# led_matrix_board.net
KiCad netlist of a schematic drawn in Altium Designer
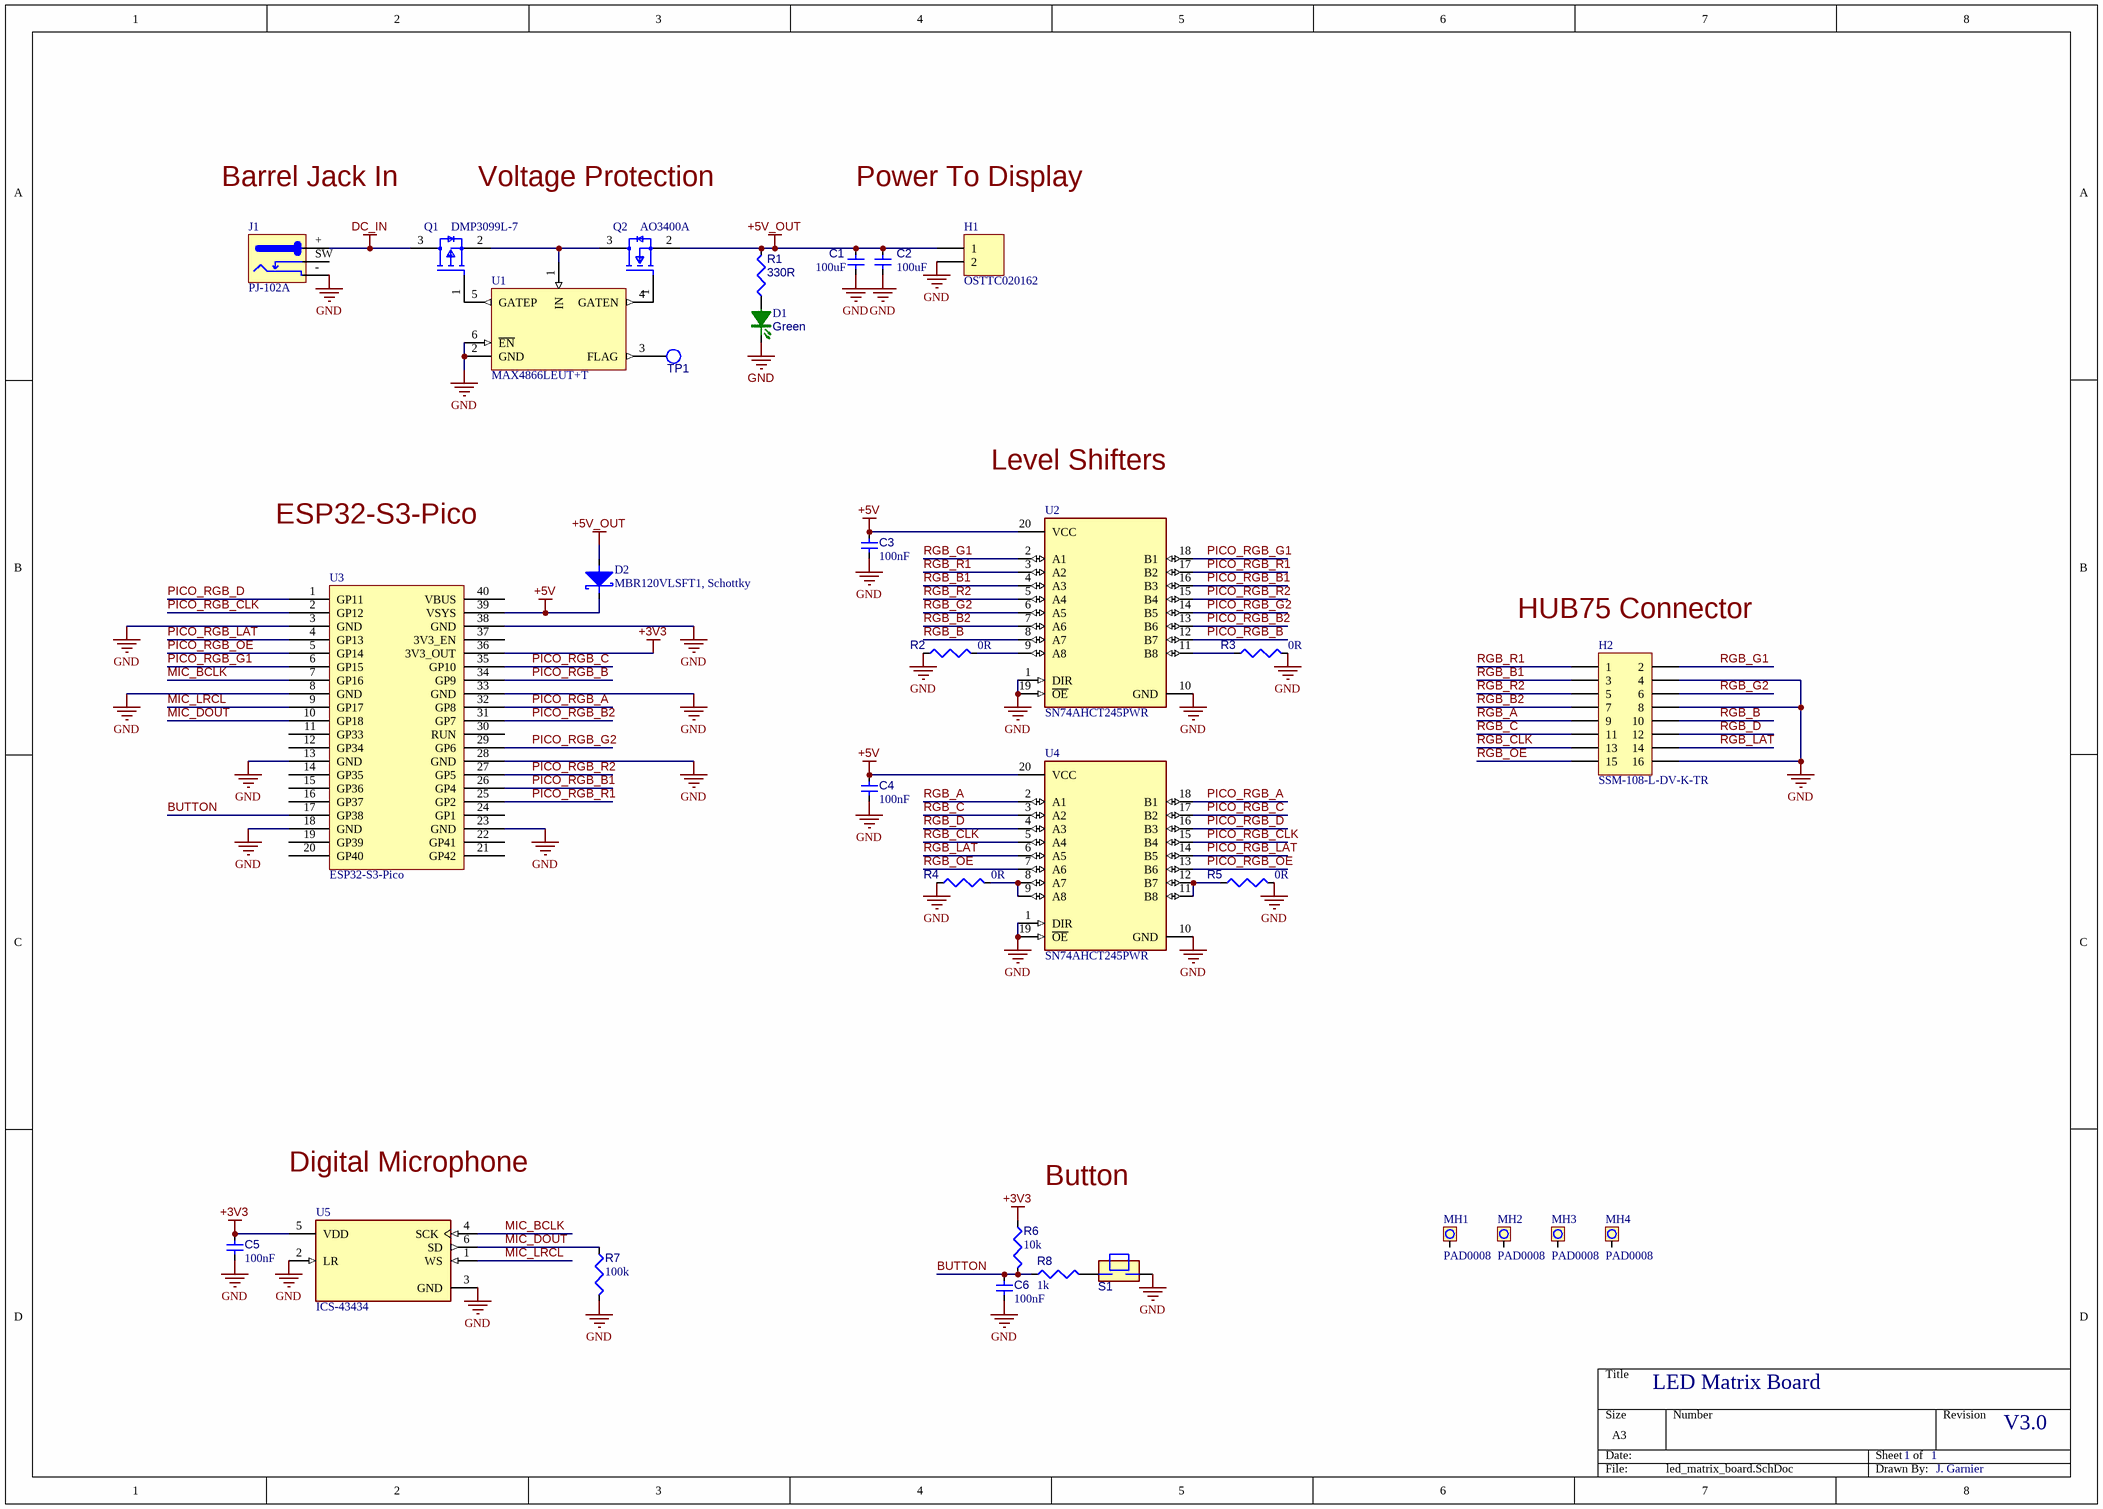
[diagram p0: led_matrix_board.SchDoc]

(export (version "E")
  (design (tool "Eeschema 10.0.6"))
  (components
    (comp (ref "C1")
      (value "100uF")
      (footprint "CAPC3225X20N")
      (description "CAP CER 100UF 10V ±20% X5R 1210")
      (fields (field (name "TOLERANCE") "20%") (field (name "VOLTAGE") "10V"))
      (libsource (lib "Morse Micro Pty Limited") (part "CAP"))
    )
    (comp (ref "C2")
      (value "100uF")
      (footprint "CAPC3225X20N")
      (description "CAP CER 100UF 10V ±20% X5R 1210")
      (fields (field (name "TOLERANCE") "20%") (field (name "VOLTAGE") "10V"))
      (libsource (lib "Morse Micro Pty Limited") (part "CAP"))
    )
    (comp (ref "C3")
      (value "100nF")
      (footprint "0603_cap")
      (description "CAP CER 100NF 10V ±10% X7R 0603")
      (fields (field (name "TOLERANCE") "10%") (field (name "VOLTAGE") "10V"))
      (libsource (lib "Morse Micro Pty Limited") (part "CAP"))
    )
    (comp (ref "C4")
      (value "100nF")
      (footprint "0603_cap")
      (description "CAP CER 100NF 10V ±10% X7R 0603")
      (fields (field (name "TOLERANCE") "10%") (field (name "VOLTAGE") "10V"))
      (libsource (lib "Morse Micro Pty Limited") (part "CAP"))
    )
    (comp (ref "C5")
      (value "100nF")
      (footprint "0603_cap")
      (description "CAP CER 100NF 10V ±10% X7R 0603")
      (fields (field (name "TOLERANCE") "10%") (field (name "VOLTAGE") "10V"))
      (libsource (lib "Morse Micro Pty Limited") (part "CAP"))
    )
    (comp (ref "C6")
      (value "100nF")
      (footprint "0603_cap")
      (description "CAP CER 100NF 10V ±10% X7R 0603")
      (fields (field (name "TOLERANCE") "10%") (field (name "VOLTAGE") "10V"))
      (libsource (lib "Morse Micro Pty Limited") (part "CAP"))
    )
    (comp (ref "D1")
      (value "Green")
      (footprint "LED_0402_GREEN")
      (description "LED GREEN 0402 SMD")
      (fields (field (name "VOLTAGE") "2.0V") (field (name "Comment") "XZVGR68W-3"))
      (libsource (lib "Morse Micro Pty Limited") (part "LED_G"))
    )
    (comp (ref "D2")
      (value "MBR120VLSFT1, Schottky")
      (footprint "SOD-123FL")
      (description "Diodes, MBR120VLSFT1 Schottky 1A 20V, Vf=0.34V")
      (fields (field (name "VOLTAGE") "20V") (field (name "Comment") "MBR120VLSFT1"))
      (libsource (lib "Morse Micro Pty Limited") (part "SCHOTTKY_DIODE"))
    )
    (comp (ref "H1")
      (value "OSTTC020162")
      (footprint "SCREW_TERM_2WAY_5MM")
      (description "CONN TERM BLOCK 5MM 2POS")
      (libsource (lib "Morse Micro Pty Limited") (part "HDR_1X2"))
    )
    (comp (ref "H2")
      (value "SSM-108-L-DV-K-TR")
      (footprint "FP-SSM-108-L-DV-K-TR-MFG")
      (description "PCB Receptacle, Board-to-Board, 2.54 mm, 2 Rows, 16 Contacts, Surface Mount")
      (libsource (lib "Morse Micro Pty Limited") (part "HDR_2X8"))
    )
    (comp (ref "J1")
      (value "PJ-102A")
      (footprint "PJ-102A")
      (description "Conn Power Jack 2.1mm PCB Mount Thru-Hole")
      (libsource (lib "Morse Micro Pty Limited") (part "2_1MM POWER"))
    )
    (comp (ref "MH1")
      (value "PAD0008")
      (footprint "MH_600_320_NPTH")
      (description "MH 6.00MM DIA 3.2MM HOLE NPTH")
      (libsource (lib "Morse Micro Pty Limited") (part "MH_600_320_NPTH"))
    )
    (comp (ref "MH2")
      (value "PAD0008")
      (footprint "MH_600_320_NPTH")
      (description "MH 6.00MM DIA 3.2MM HOLE NPTH")
      (libsource (lib "Morse Micro Pty Limited") (part "MH_600_320_NPTH"))
    )
    (comp (ref "MH3")
      (value "PAD0008")
      (footprint "MH_600_320_NPTH")
      (description "MH 6.00MM DIA 3.2MM HOLE NPTH")
      (libsource (lib "Morse Micro Pty Limited") (part "MH_600_320_NPTH"))
    )
    (comp (ref "MH4")
      (value "PAD0008")
      (footprint "MH_600_320_NPTH")
      (description "MH 6.00MM DIA 3.2MM HOLE NPTH")
      (libsource (lib "Morse Micro Pty Limited") (part "MH_600_320_NPTH"))
    )
    (comp (ref "Q1")
      (value "DMP3099L-7")
      (footprint "FP-SOT23-IPC_C")
      (description "DMP3099L Series 30 V 65 mOhm P-Channel Enhancement Mode Mosfet - SOT-23-3")
      (libsource (lib "Morse Micro Pty Limited") (part "d876440acba04c58a9f817a20952145"))
    )
    (comp (ref "Q2")
      (value "AO3400A")
      (footprint "FP-SOT23-IPC_C")
      (description "Trans MOSFET N-CH 30V 5.7A 3-Pin SOT-23")
      (libsource (lib "Morse Micro Pty Limited") (part "0a9ea7c96deaaede766a5b531c28de0"))
    )
    (comp (ref "R1")
      (value "330R")
      (footprint "0402_res")
      (description "RES SMD 330R OHM ±1% 1/16W 0402")
      (fields (field (name "POWER") "1/16W") (field (name "TOLERANCE") "1%"))
      (libsource (lib "Morse Micro Pty Limited") (part "RES"))
    )
    (comp (ref "R2")
      (value "0R")
      (footprint "0603_res")
      (description "RES SMD 0R OHM ±1% 1/10W 0603")
      (fields (field (name "TOLERANCE") "1%") (field (name "POWER") "1/10W"))
      (libsource (lib "Morse Micro Pty Limited") (part "RES"))
    )
    (comp (ref "R3")
      (value "0R")
      (footprint "0603_res")
      (description "RES SMD 0R OHM ±1% 1/10W 0603")
      (fields (field (name "TOLERANCE") "1%") (field (name "POWER") "1/10W"))
      (libsource (lib "Morse Micro Pty Limited") (part "RES"))
    )
    (comp (ref "R4")
      (value "0R")
      (footprint "0603_res")
      (description "RES SMD 0R OHM ±1% 1/10W 0603")
      (fields (field (name "TOLERANCE") "1%") (field (name "POWER") "1/10W"))
      (libsource (lib "Morse Micro Pty Limited") (part "RES"))
    )
    (comp (ref "R5")
      (value "0R")
      (footprint "0603_res")
      (description "RES SMD 0R OHM ±1% 1/10W 0603")
      (fields (field (name "TOLERANCE") "1%") (field (name "POWER") "1/10W"))
      (libsource (lib "Morse Micro Pty Limited") (part "RES"))
    )
    (comp (ref "R6")
      (value "10k")
      (footprint "0603_res")
      (description "RES SMD 10K OHM ±1% 1/10W 0603")
      (fields (field (name "POWER") "1/10W") (field (name "TOLERANCE") "1%"))
      (libsource (lib "Morse Micro Pty Limited") (part "RES"))
    )
    (comp (ref "R7")
      (value "100k")
      (footprint "0603_res")
      (description "RES SMD 100K OHM ±1% 1/10W 0603")
      (fields (field (name "POWER") "1/10W") (field (name "TOLERANCE") "1%"))
      (libsource (lib "Morse Micro Pty Limited") (part "RES"))
    )
    (comp (ref "R8")
      (value "1k")
      (footprint "0603_res")
      (description "RES SMD 1K OHM ±0 .1% 1/10W 0603")
      (fields (field (name "TOLERANCE") "0 .1%") (field (name "POWER") "1/10W"))
      (libsource (lib "Morse Micro Pty Limited") (part "RES"))
    )
    (comp (ref "S1")
      (value "EVQ-PF206K")
      (footprint "EVQ-PF206K")
      (description "SW, Tactile 15V@20mA, EVQ-PF, Through Hole, R/A, 7.5x7.1x5.85mm")
      (libsource (lib "Morse Micro Pty Limited") (part "SW_PB"))
    )
    (comp (ref "TP1")
      (value "PAD0035")
      (footprint "TP_40_SMT")
      (description "40mil 1mm SMD Test Point")
      (libsource (lib "Morse Micro Pty Limited") (part "TP_20_SMT"))
    )
    (comp (ref "U1")
      (value "MAX4866LEUT+T")
      (footprint "MAX4866LEUT+T-Footprint-1")
      (description "Overvoltage Protection Controllers with Reverse Polarity Protection")
      (libsource (lib "Morse Micro Pty Limited") (part "MAX4866LEUT+T-Symbol-1"))
    )
    (comp (ref "U2")
      (value "SN74AHCT245PWR")
      (footprint "FP-PW0020A-IPC_A")
      (description "8mA 8 4.5V~5.5V 8mA 1 TSSOP-20 Buffer/Driver/Transceiver ROHS")
      (libsource (lib "Morse Micro Pty Limited") (part "f8b0c07ade4f6b8d62f3b9458d8db27"))
    )
    (comp (ref "U3")
      (value "ESP32-S3-Pico")
      (footprint "ESP32-S3-Pico")
      (description "ESP32-S3-Pico Module.")
      (libsource (lib "Morse Micro Pty Limited") (part "ESP32-S3-Pico"))
    )
    (comp (ref "U4")
      (value "SN74AHCT245PWR")
      (footprint "FP-PW0020A-IPC_A")
      (description "8mA 8 4.5V~5.5V 8mA 1 TSSOP-20 Buffer/Driver/Transceiver ROHS")
      (libsource (lib "Morse Micro Pty Limited") (part "f8b0c07ade4f6b8d62f3b9458d8db27"))
    )
    (comp (ref "U5")
      (value "ICS-43434")
      (footprint "FP-ICS-43434-MFG")
      (description "Mic Omni-Directional -26dB 3.63V Rectangular Solder Pad T/R")
      (libsource (lib "Morse Micro Pty Limited") (part "ae05e933d23a1a1b08b70095a55dc98"))
    )
  )
  (nets
    (net (code "1") (name "+3V3") (class "Default")
      (node (ref "C5") (pin "1") (pinfunction "1_1") (pintype "passive"))
      (node (ref "R6") (pin "1") (pinfunction "1_1") (pintype "passive"))
      (node (ref "U3") (pin "36") (pinfunction "3V3_OUT_36") (pintype "passive"))
      (node (ref "U5") (pin "5") (pinfunction "VDD_5") (pintype "power_in"))
    )
    (net (code "2") (name "+5V") (class "Default")
      (node (ref "C3") (pin "1") (pinfunction "1_1") (pintype "passive"))
      (node (ref "C4") (pin "1") (pinfunction "1_1") (pintype "passive"))
      (node (ref "D2") (pin "K") (pinfunction "K_K") (pintype "passive"))
      (node (ref "U2") (pin "20") (pinfunction "VCC_20") (pintype "power_in"))
      (node (ref "U3") (pin "39") (pinfunction "VSYS_39") (pintype "passive"))
      (node (ref "U4") (pin "20") (pinfunction "VCC_20") (pintype "power_in"))
    )
    (net (code "3") (name "+5V_OUT") (class "Default")
      (node (ref "C1") (pin "1") (pinfunction "1_1") (pintype "passive"))
      (node (ref "C2") (pin "1") (pinfunction "1_1") (pintype "passive"))
      (node (ref "D2") (pin "A") (pinfunction "A_A") (pintype "passive"))
      (node (ref "H1") (pin "1") (pinfunction "1_1") (pintype "passive"))
      (node (ref "Q2") (pin "2") (pinfunction "S_2") (pintype "passive"))
      (node (ref "R1") (pin "2") (pinfunction "2_2") (pintype "passive"))
    )
    (net (code "4") (name "/BUTTON") (class "Default")
      (node (ref "C6") (pin "1") (pinfunction "1_1") (pintype "passive"))
      (node (ref "R6") (pin "2") (pinfunction "2_2") (pintype "passive"))
      (node (ref "R8") (pin "1") (pinfunction "1_1") (pintype "passive"))
      (node (ref "U3") (pin "17") (pinfunction "GP38_17") (pintype "passive"))
    )
    (net (code "5") (name "/MIC_BCLK") (class "Default")
      (node (ref "U3") (pin "7") (pinfunction "GP16_7") (pintype "passive"))
      (node (ref "U5") (pin "4") (pinfunction "SCK_4") (pintype "input"))
    )
    (net (code "6") (name "/MIC_DOUT") (class "Default")
      (node (ref "R7") (pin "1") (pinfunction "1_1") (pintype "passive"))
      (node (ref "U3") (pin "10") (pinfunction "GP18_10") (pintype "passive"))
      (node (ref "U5") (pin "6") (pinfunction "SD_6") (pintype "output"))
    )
    (net (code "7") (name "/MIC_LRCL") (class "Default")
      (node (ref "U3") (pin "9") (pinfunction "GP17_9") (pintype "passive"))
      (node (ref "U5") (pin "1") (pinfunction "WS_1") (pintype "input"))
    )
    (net (code "8") (name "/PICO_RGB_A") (class "Default")
      (node (ref "U3") (pin "32") (pinfunction "GP8_32") (pintype "passive"))
      (node (ref "U4") (pin "18") (pinfunction "B1_18") (pintype "bidirectional"))
    )
    (net (code "9") (name "/PICO_RGB_B") (class "Default")
      (node (ref "U2") (pin "12") (pinfunction "B7_12") (pintype "bidirectional"))
      (node (ref "U3") (pin "34") (pinfunction "GP9_34") (pintype "passive"))
    )
    (net (code "10") (name "/PICO_RGB_B1") (class "Default")
      (node (ref "U2") (pin "16") (pinfunction "B3_16") (pintype "bidirectional"))
      (node (ref "U3") (pin "26") (pinfunction "GP4_26") (pintype "passive"))
    )
    (net (code "11") (name "/PICO_RGB_B2") (class "Default")
      (node (ref "U2") (pin "13") (pinfunction "B6_13") (pintype "bidirectional"))
      (node (ref "U3") (pin "31") (pinfunction "GP7_31") (pintype "passive"))
    )
    (net (code "12") (name "/PICO_RGB_C") (class "Default")
      (node (ref "U3") (pin "35") (pinfunction "GP10_35") (pintype "passive"))
      (node (ref "U4") (pin "17") (pinfunction "B2_17") (pintype "bidirectional"))
    )
    (net (code "13") (name "/PICO_RGB_CLK") (class "Default")
      (node (ref "U3") (pin "2") (pinfunction "GP12_2") (pintype "passive"))
      (node (ref "U4") (pin "15") (pinfunction "B4_15") (pintype "bidirectional"))
    )
    (net (code "14") (name "/PICO_RGB_D") (class "Default")
      (node (ref "U3") (pin "1") (pinfunction "GP11_1") (pintype "passive"))
      (node (ref "U4") (pin "16") (pinfunction "B3_16") (pintype "bidirectional"))
    )
    (net (code "15") (name "/PICO_RGB_G1") (class "Default")
      (node (ref "U2") (pin "18") (pinfunction "B1_18") (pintype "bidirectional"))
      (node (ref "U3") (pin "6") (pinfunction "GP15_6") (pintype "passive"))
    )
    (net (code "16") (name "/PICO_RGB_G2") (class "Default")
      (node (ref "U2") (pin "14") (pinfunction "B5_14") (pintype "bidirectional"))
      (node (ref "U3") (pin "29") (pinfunction "GP6_29") (pintype "passive"))
    )
    (net (code "17") (name "/PICO_RGB_LAT") (class "Default")
      (node (ref "U3") (pin "4") (pinfunction "GP13_4") (pintype "passive"))
      (node (ref "U4") (pin "14") (pinfunction "B5_14") (pintype "bidirectional"))
    )
    (net (code "18") (name "/PICO_RGB_OE") (class "Default")
      (node (ref "U3") (pin "5") (pinfunction "GP14_5") (pintype "passive"))
      (node (ref "U4") (pin "13") (pinfunction "B6_13") (pintype "bidirectional"))
    )
    (net (code "19") (name "/PICO_RGB_R1") (class "Default")
      (node (ref "U2") (pin "17") (pinfunction "B2_17") (pintype "bidirectional"))
      (node (ref "U3") (pin "25") (pinfunction "GP2_25") (pintype "passive"))
    )
    (net (code "20") (name "/PICO_RGB_R2") (class "Default")
      (node (ref "U2") (pin "15") (pinfunction "B4_15") (pintype "bidirectional"))
      (node (ref "U3") (pin "27") (pinfunction "GP5_27") (pintype "passive"))
    )
    (net (code "21") (name "/RGB_A") (class "Default")
      (node (ref "H2") (pin "9") (pinfunction "9_9") (pintype "passive"))
      (node (ref "U4") (pin "2") (pinfunction "A1_2") (pintype "bidirectional"))
    )
    (net (code "22") (name "/RGB_B") (class "Default")
      (node (ref "H2") (pin "10") (pinfunction "10_10") (pintype "passive"))
      (node (ref "U2") (pin "8") (pinfunction "A7_8") (pintype "bidirectional"))
    )
    (net (code "23") (name "/RGB_B1") (class "Default")
      (node (ref "H2") (pin "3") (pinfunction "3_3") (pintype "passive"))
      (node (ref "U2") (pin "4") (pinfunction "A3_4") (pintype "bidirectional"))
    )
    (net (code "24") (name "/RGB_B2") (class "Default")
      (node (ref "H2") (pin "7") (pinfunction "7_7") (pintype "passive"))
      (node (ref "U2") (pin "7") (pinfunction "A6_7") (pintype "bidirectional"))
    )
    (net (code "25") (name "/RGB_C") (class "Default")
      (node (ref "H2") (pin "11") (pinfunction "11_11") (pintype "passive"))
      (node (ref "U4") (pin "3") (pinfunction "A2_3") (pintype "bidirectional"))
    )
    (net (code "26") (name "/RGB_CLK") (class "Default")
      (node (ref "H2") (pin "13") (pinfunction "13_13") (pintype "passive"))
      (node (ref "U4") (pin "5") (pinfunction "A4_5") (pintype "bidirectional"))
    )
    (net (code "27") (name "/RGB_D") (class "Default")
      (node (ref "H2") (pin "12") (pinfunction "12_12") (pintype "passive"))
      (node (ref "U4") (pin "4") (pinfunction "A3_4") (pintype "bidirectional"))
    )
    (net (code "28") (name "/RGB_G1") (class "Default")
      (node (ref "H2") (pin "2") (pinfunction "2_2") (pintype "passive"))
      (node (ref "U2") (pin "2") (pinfunction "A1_2") (pintype "bidirectional"))
    )
    (net (code "29") (name "/RGB_G2") (class "Default")
      (node (ref "H2") (pin "6") (pinfunction "6_6") (pintype "passive"))
      (node (ref "U2") (pin "6") (pinfunction "A5_6") (pintype "bidirectional"))
    )
    (net (code "30") (name "/RGB_LAT") (class "Default")
      (node (ref "H2") (pin "14") (pinfunction "14_14") (pintype "passive"))
      (node (ref "U4") (pin "6") (pinfunction "A5_6") (pintype "bidirectional"))
    )
    (net (code "31") (name "/RGB_OE") (class "Default")
      (node (ref "H2") (pin "15") (pinfunction "15_15") (pintype "passive"))
      (node (ref "U4") (pin "7") (pinfunction "A6_7") (pintype "bidirectional"))
    )
    (net (code "32") (name "/RGB_R1") (class "Default")
      (node (ref "H2") (pin "1") (pinfunction "1_1") (pintype "passive"))
      (node (ref "U2") (pin "3") (pinfunction "A2_3") (pintype "bidirectional"))
    )
    (net (code "33") (name "/RGB_R2") (class "Default")
      (node (ref "H2") (pin "5") (pinfunction "5_5") (pintype "passive"))
      (node (ref "U2") (pin "5") (pinfunction "A4_5") (pintype "bidirectional"))
    )
    (net (code "34") (name "DC_IN") (class "Default")
      (node (ref "J1") (pin "+") (pinfunction "+_+") (pintype "passive"))
      (node (ref "Q1") (pin "3") (pinfunction "D_3") (pintype "passive"))
    )
    (net (code "35") (name "GND") (class "Default")
      (node (ref "C1") (pin "2") (pinfunction "2_2") (pintype "passive"))
      (node (ref "C2") (pin "2") (pinfunction "2_2") (pintype "passive"))
      (node (ref "C3") (pin "2") (pinfunction "2_2") (pintype "passive"))
      (node (ref "C4") (pin "2") (pinfunction "2_2") (pintype "passive"))
      (node (ref "C5") (pin "2") (pinfunction "2_2") (pintype "passive"))
      (node (ref "C6") (pin "2") (pinfunction "2_2") (pintype "passive"))
      (node (ref "D1") (pin "K") (pinfunction "2_K") (pintype "passive"))
      (node (ref "H1") (pin "2") (pinfunction "2_2") (pintype "passive"))
      (node (ref "H2") (pin "16") (pinfunction "16_16") (pintype "passive"))
      (node (ref "H2") (pin "4") (pinfunction "4_4") (pintype "passive"))
      (node (ref "H2") (pin "8") (pinfunction "8_8") (pintype "passive"))
      (node (ref "J1") (pin "-") (pinfunction "-_-") (pintype "passive"))
      (node (ref "R2") (pin "1") (pinfunction "1_1") (pintype "passive"))
      (node (ref "R3") (pin "1") (pinfunction "1_1") (pintype "passive"))
      (node (ref "R4") (pin "1") (pinfunction "1_1") (pintype "passive"))
      (node (ref "R5") (pin "2") (pinfunction "2_2") (pintype "passive"))
      (node (ref "R7") (pin "2") (pinfunction "2_2") (pintype "passive"))
      (node (ref "S1") (pin "2") (pinfunction "2_2") (pintype "passive"))
      (node (ref "U1") (pin "2") (pinfunction "GND_2") (pintype "power_in"))
      (node (ref "U1") (pin "6") (pinfunction "~{EN}_6") (pintype "input"))
      (node (ref "U2") (pin "1") (pinfunction "DIR_1") (pintype "input"))
      (node (ref "U2") (pin "10") (pinfunction "GND_10") (pintype "power_in"))
      (node (ref "U2") (pin "19") (pinfunction "~{OE}_19") (pintype "input"))
      (node (ref "U3") (pin "13") (pinfunction "GND_13") (pintype "passive"))
      (node (ref "U3") (pin "18") (pinfunction "GND_18") (pintype "passive"))
      (node (ref "U3") (pin "23") (pinfunction "GND_23") (pintype "passive"))
      (node (ref "U3") (pin "28") (pinfunction "GND_28") (pintype "passive"))
      (node (ref "U3") (pin "3") (pinfunction "GND_3") (pintype "passive"))
      (node (ref "U3") (pin "33") (pinfunction "GND_33") (pintype "passive"))
      (node (ref "U3") (pin "38") (pinfunction "GND_38") (pintype "passive"))
      (node (ref "U3") (pin "8") (pinfunction "GND_8") (pintype "passive"))
      (node (ref "U4") (pin "1") (pinfunction "DIR_1") (pintype "input"))
      (node (ref "U4") (pin "10") (pinfunction "GND_10") (pintype "power_in"))
      (node (ref "U4") (pin "19") (pinfunction "~{OE}_19") (pintype "input"))
      (node (ref "U5") (pin "2") (pinfunction "LR_2") (pintype "input"))
      (node (ref "U5") (pin "3") (pinfunction "GND_3") (pintype "power_in"))
    )
    (net (code "36") (name "Net-(D1-1)") (class "Default")
      (node (ref "D1") (pin "A") (pinfunction "1_A") (pintype "passive"))
      (node (ref "R1") (pin "1") (pinfunction "1_1") (pintype "passive"))
    )
    (net (code "37") (name "Net-(Q1-G)") (class "Default")
      (node (ref "Q1") (pin "1") (pinfunction "G_1") (pintype "passive"))
      (node (ref "U1") (pin "5") (pinfunction "GATEP_5") (pintype "output"))
    )
    (net (code "38") (name "Net-(Q1-S)") (class "Default")
      (node (ref "Q1") (pin "2") (pinfunction "S_2") (pintype "passive"))
      (node (ref "Q2") (pin "3") (pinfunction "D_3") (pintype "passive"))
      (node (ref "U1") (pin "1") (pinfunction "IN_1") (pintype "input"))
    )
    (net (code "39") (name "Net-(Q2-G)") (class "Default")
      (node (ref "Q2") (pin "1") (pinfunction "G_1") (pintype "passive"))
      (node (ref "U1") (pin "4") (pinfunction "GATEN_4") (pintype "output"))
    )
    (net (code "40") (name "Net-(R8-Pad2)") (class "Default")
      (node (ref "R8") (pin "2") (pinfunction "2_2") (pintype "passive"))
      (node (ref "S1") (pin "1") (pinfunction "1_1") (pintype "passive"))
    )
    (net (code "41") (name "Net-(U1-FLAG)") (class "Default")
      (node (ref "TP1") (pin "1") (pinfunction "1_1") (pintype "passive"))
      (node (ref "U1") (pin "3") (pinfunction "FLAG_3") (pintype "output"))
    )
    (net (code "42") (name "Net-(U2-A8)") (class "Default")
      (node (ref "R2") (pin "2") (pinfunction "2_2") (pintype "passive"))
      (node (ref "U2") (pin "9") (pinfunction "A8_9") (pintype "bidirectional"))
    )
    (net (code "43") (name "Net-(U2-B8)") (class "Default")
      (node (ref "R3") (pin "2") (pinfunction "2_2") (pintype "passive"))
      (node (ref "U2") (pin "11") (pinfunction "B8_11") (pintype "bidirectional"))
    )
    (net (code "44") (name "Net-(U4-A7)") (class "Default")
      (node (ref "R4") (pin "2") (pinfunction "2_2") (pintype "passive"))
      (node (ref "U4") (pin "8") (pinfunction "A7_8") (pintype "bidirectional"))
      (node (ref "U4") (pin "9") (pinfunction "A8_9") (pintype "bidirectional"))
    )
    (net (code "45") (name "Net-(U4-B7)") (class "Default")
      (node (ref "R5") (pin "1") (pinfunction "1_1") (pintype "passive"))
      (node (ref "U4") (pin "11") (pinfunction "B8_11") (pintype "bidirectional"))
      (node (ref "U4") (pin "12") (pinfunction "B7_12") (pintype "bidirectional"))
    )
    (net (code "46") (name "unconnected-(J1-PadSW)") (class "Default")
      (node (ref "J1") (pin "SW") (pinfunction "SW_SW") (pintype "passive"))
    )
    (net (code "47") (name "unconnected-(MH1-Pad1)") (class "Default")
      (node (ref "MH1") (pin "1") (pinfunction "1_1") (pintype "passive"))
    )
    (net (code "48") (name "unconnected-(MH2-Pad1)") (class "Default")
      (node (ref "MH2") (pin "1") (pinfunction "1_1") (pintype "passive"))
    )
    (net (code "49") (name "unconnected-(MH3-Pad1)") (class "Default")
      (node (ref "MH3") (pin "1") (pinfunction "1_1") (pintype "passive"))
    )
    (net (code "50") (name "unconnected-(MH4-Pad1)") (class "Default")
      (node (ref "MH4") (pin "1") (pinfunction "1_1") (pintype "passive"))
    )
    (net (code "51") (name "unconnected-(U3-3V3_EN-Pad37)") (class "Default")
      (node (ref "U3") (pin "37") (pinfunction "3V3_EN_37") (pintype "passive"))
    )
    (net (code "52") (name "unconnected-(U3-GP1-Pad24)") (class "Default")
      (node (ref "U3") (pin "24") (pinfunction "GP1_24") (pintype "passive"))
    )
    (net (code "53") (name "unconnected-(U3-GP33-Pad11)") (class "Default")
      (node (ref "U3") (pin "11") (pinfunction "GP33_11") (pintype "passive"))
    )
    (net (code "54") (name "unconnected-(U3-GP34-Pad12)") (class "Default")
      (node (ref "U3") (pin "12") (pinfunction "GP34_12") (pintype "passive"))
    )
    (net (code "55") (name "unconnected-(U3-GP35-Pad14)") (class "Default")
      (node (ref "U3") (pin "14") (pinfunction "GP35_14") (pintype "passive"))
    )
    (net (code "56") (name "unconnected-(U3-GP36-Pad15)") (class "Default")
      (node (ref "U3") (pin "15") (pinfunction "GP36_15") (pintype "passive"))
    )
    (net (code "57") (name "unconnected-(U3-GP37-Pad16)") (class "Default")
      (node (ref "U3") (pin "16") (pinfunction "GP37_16") (pintype "passive"))
    )
    (net (code "58") (name "unconnected-(U3-GP39-Pad19)") (class "Default")
      (node (ref "U3") (pin "19") (pinfunction "GP39_19") (pintype "passive"))
    )
    (net (code "59") (name "unconnected-(U3-GP40-Pad20)") (class "Default")
      (node (ref "U3") (pin "20") (pinfunction "GP40_20") (pintype "passive"))
    )
    (net (code "60") (name "unconnected-(U3-GP41-Pad22)") (class "Default")
      (node (ref "U3") (pin "22") (pinfunction "GP41_22") (pintype "passive"))
    )
    (net (code "61") (name "unconnected-(U3-GP42-Pad21)") (class "Default")
      (node (ref "U3") (pin "21") (pinfunction "GP42_21") (pintype "passive"))
    )
    (net (code "62") (name "unconnected-(U3-RUN-Pad30)") (class "Default")
      (node (ref "U3") (pin "30") (pinfunction "RUN_30") (pintype "passive"))
    )
    (net (code "63") (name "unconnected-(U3-VBUS-Pad40)") (class "Default")
      (node (ref "U3") (pin "40") (pinfunction "VBUS_40") (pintype "passive"))
    )
  )
)
